# MAX7400_Test_Board.net
KiCad netlist of a schematic drawn in EAGLE
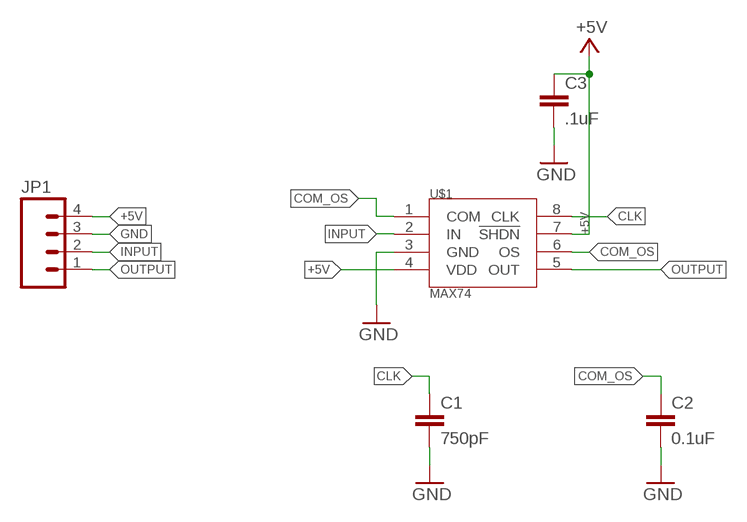
[diagram p0: schematic, sheet 1]

(export (version "E")
  (design (tool "Eeschema 10.0.6"))
  (components
    (comp (ref "C1")
      (value "750pF")
      (footprint "eagle-import:0603-CAP")
      (libsource (lib "eagle-import") (part "CAP0603-CAP"))
    )
    (comp (ref "C2")
      (value "0.1uF")
      (footprint "eagle-import:0603-CAP")
      (libsource (lib "eagle-import") (part "CAP0603-CAP"))
    )
    (comp (ref "C3")
      (value ".1uF")
      (footprint "eagle-import:0603-CAP")
      (libsource (lib "eagle-import") (part "CAP0603-CAP"))
    )
    (comp (ref "JP1")
      (value "M04")
      (footprint "eagle-import:1X04")
      (libsource (lib "eagle-import") (part "M04"))
    )
    (comp (ref "U$1")
      (value "MAX74")
      (footprint "eagle-import:SOP8")
      (libsource (lib "eagle-import") (part "MAX7400"))
    )
  )
  (nets
    (net (code "1") (name "+5V") (class "Default")
      (node (ref "C3") (pin "1") (pinfunction "1_1") (pintype "passive"))
      (node (ref "JP1") (pin "4") (pinfunction "4_4") (pintype "passive"))
      (node (ref "U$1") (pin "4") (pinfunction "VDD_4") (pintype "bidirectional"))
      (node (ref "U$1") (pin "7") (pinfunction "~{SHDN}_7") (pintype "bidirectional"))
    )
    (net (code "2") (name "CLK") (class "Default")
      (node (ref "C1") (pin "1") (pinfunction "1_1") (pintype "passive"))
      (node (ref "U$1") (pin "8") (pinfunction "CLK_8") (pintype "bidirectional"))
    )
    (net (code "3") (name "COM_OS") (class "Default")
      (node (ref "C2") (pin "1") (pinfunction "1_1") (pintype "passive"))
      (node (ref "U$1") (pin "1") (pinfunction "COM_1") (pintype "bidirectional"))
      (node (ref "U$1") (pin "6") (pinfunction "OS_6") (pintype "bidirectional"))
    )
    (net (code "4") (name "GND") (class "Default")
      (node (ref "C1") (pin "2") (pinfunction "2_2") (pintype "passive"))
      (node (ref "C2") (pin "2") (pinfunction "2_2") (pintype "passive"))
      (node (ref "C3") (pin "2") (pinfunction "2_2") (pintype "passive"))
      (node (ref "JP1") (pin "3") (pinfunction "3_3") (pintype "passive"))
      (node (ref "U$1") (pin "3") (pinfunction "GND_3") (pintype "bidirectional"))
    )
    (net (code "5") (name "INPUT") (class "Default")
      (node (ref "JP1") (pin "2") (pinfunction "2_2") (pintype "passive"))
      (node (ref "U$1") (pin "2") (pinfunction "IN_2") (pintype "bidirectional"))
    )
    (net (code "6") (name "OUTPUT") (class "Default")
      (node (ref "JP1") (pin "1") (pinfunction "1_1") (pintype "passive"))
      (node (ref "U$1") (pin "5") (pinfunction "OUT_5") (pintype "bidirectional"))
    )
  )
)
